# wm8804_breakout.net
KiCad netlist of a schematic drawn in EAGLE
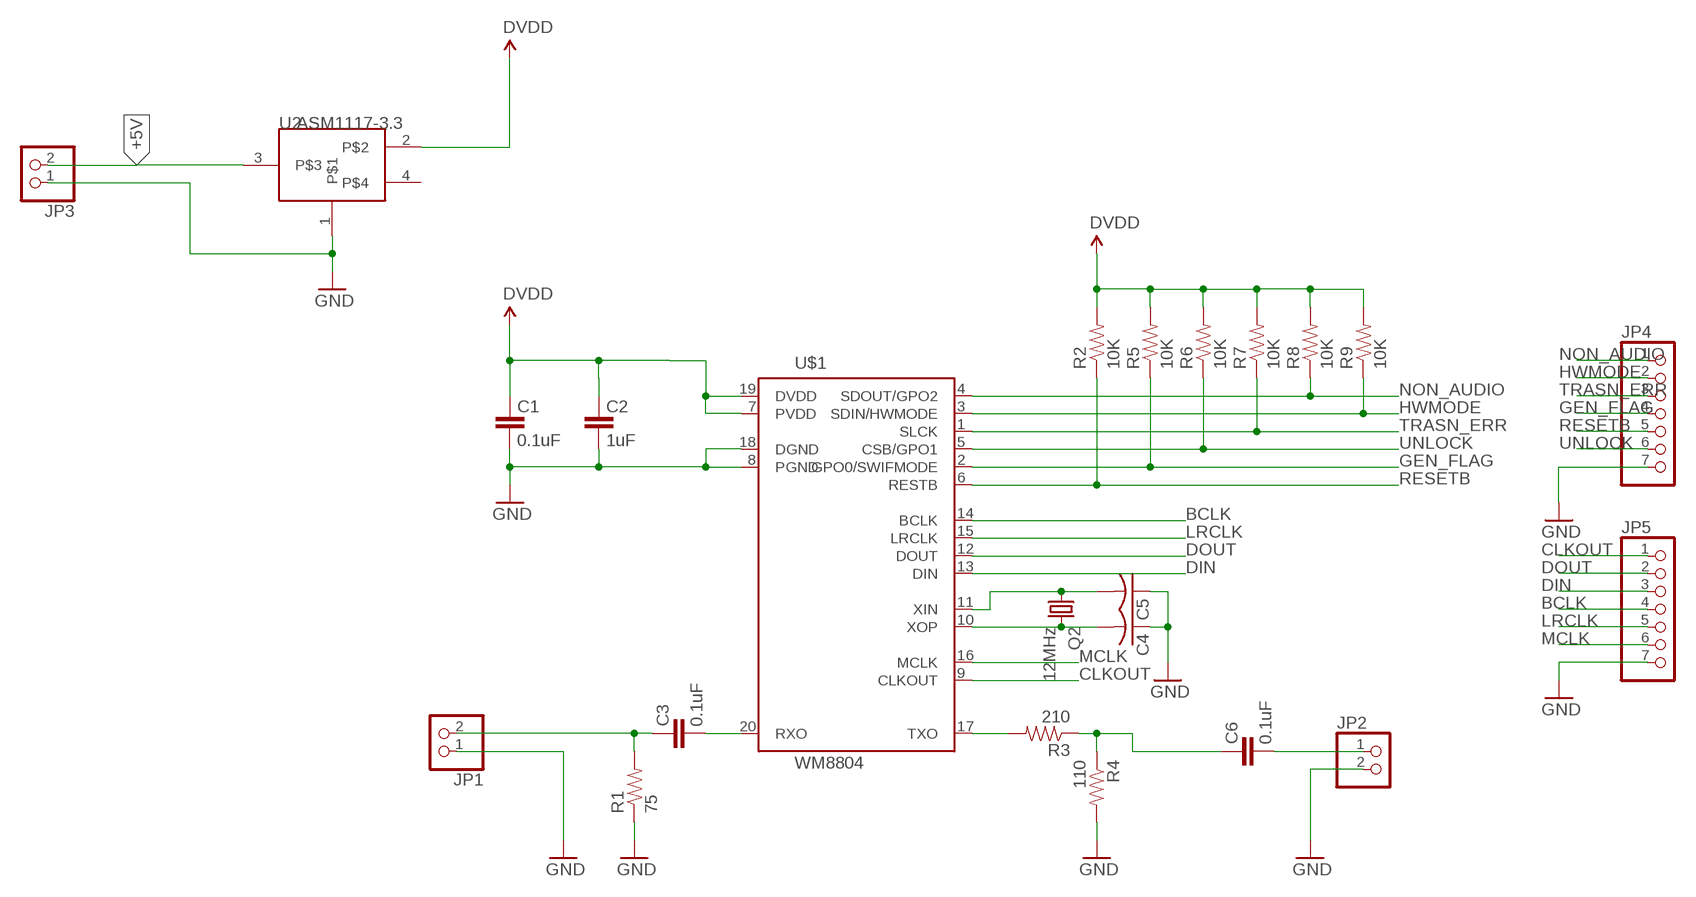
[diagram p0: schematic, sheet 1]

(export (version "E")
  (design (tool "Eeschema 10.0.6"))
  (components
    (comp (ref "C1")
      (value "0.1uF")
      (footprint "eagle-import:0805")
      (libsource (lib "eagle-import") (part "CAP0805"))
    )
    (comp (ref "C2")
      (value "1uF")
      (footprint "eagle-import:0805")
      (libsource (lib "eagle-import") (part "CAP0805"))
    )
    (comp (ref "C3")
      (value "0.1uF")
      (footprint "eagle-import:0805")
      (libsource (lib "eagle-import") (part "CAP0805"))
    )
    (comp (ref "C4")
      (value "C-USC0805")
      (footprint "eagle-import:C0805")
      (libsource (lib "eagle-import") (part "C-USC0805"))
    )
    (comp (ref "C5")
      (value "C-USC0805")
      (footprint "eagle-import:C0805")
      (libsource (lib "eagle-import") (part "C-USC0805"))
    )
    (comp (ref "C6")
      (value "0.1uF")
      (footprint "eagle-import:0805")
      (libsource (lib "eagle-import") (part "CAP0805"))
    )
    (comp (ref "JP1")
      (value "PINHD-1X2")
      (footprint "eagle-import:1X02")
      (libsource (lib "eagle-import") (part "PINHD-1X2"))
    )
    (comp (ref "JP2")
      (value "PINHD-1X2")
      (footprint "eagle-import:1X02")
      (libsource (lib "eagle-import") (part "PINHD-1X2"))
    )
    (comp (ref "JP3")
      (value "PINHD-1X2")
      (footprint "eagle-import:1X02")
      (libsource (lib "eagle-import") (part "PINHD-1X2"))
    )
    (comp (ref "JP4")
      (value "PINHD-1X7")
      (footprint "eagle-import:1X07")
      (libsource (lib "eagle-import") (part "PINHD-1X7"))
    )
    (comp (ref "JP5")
      (value "PINHD-1X7")
      (footprint "eagle-import:1X07")
      (libsource (lib "eagle-import") (part "PINHD-1X7"))
    )
    (comp (ref "Q2")
      (value "12MHz")
      (footprint "eagle-import:CTS406")
      (libsource (lib "eagle-import") (part "CRYSTALCTS406"))
    )
    (comp (ref "R1")
      (value "75")
      (footprint "eagle-import:0805")
      (libsource (lib "eagle-import") (part "RESISTOR"))
    )
    (comp (ref "R2")
      (value "10K")
      (footprint "eagle-import:0805")
      (libsource (lib "eagle-import") (part "RESISTOR"))
    )
    (comp (ref "R3")
      (value "210")
      (footprint "eagle-import:0805")
      (libsource (lib "eagle-import") (part "RESISTOR"))
    )
    (comp (ref "R4")
      (value "110")
      (footprint "eagle-import:0805")
      (libsource (lib "eagle-import") (part "RESISTOR"))
    )
    (comp (ref "R5")
      (value "10K")
      (footprint "eagle-import:0805")
      (libsource (lib "eagle-import") (part "RESISTOR"))
    )
    (comp (ref "R6")
      (value "10K")
      (footprint "eagle-import:0805")
      (libsource (lib "eagle-import") (part "RESISTOR"))
    )
    (comp (ref "R7")
      (value "10K")
      (footprint "eagle-import:0805")
      (libsource (lib "eagle-import") (part "RESISTOR"))
    )
    (comp (ref "R8")
      (value "10K")
      (footprint "eagle-import:0805")
      (libsource (lib "eagle-import") (part "RESISTOR"))
    )
    (comp (ref "R9")
      (value "10K")
      (footprint "eagle-import:0805")
      (libsource (lib "eagle-import") (part "RESISTOR"))
    )
    (comp (ref "U$1")
      (value "WM8804")
      (footprint "eagle-import:SSOP20")
      (libsource (lib "eagle-import") (part "WM8804"))
    )
    (comp (ref "U2")
      (value "ASM1117-3.3")
      (footprint "eagle-import:SOT223")
      (libsource (lib "eagle-import") (part "ASM1117-3.3"))
    )
  )
  (nets
    (net (code "1") (name "+5V") (class "Default")
      (node (ref "JP3") (pin "2") (pinfunction "2_2") (pintype "passive"))
      (node (ref "U2") (pin "3") (pinfunction "P$3_3") (pintype "bidirectional"))
    )
    (net (code "2") (name "/BCLK") (class "Default")
      (node (ref "JP5") (pin "4") (pinfunction "4_4") (pintype "passive"))
      (node (ref "U$1") (pin "14") (pinfunction "BCLK_14") (pintype "bidirectional"))
    )
    (net (code "3") (name "/CLKOUT") (class "Default")
      (node (ref "JP5") (pin "1") (pinfunction "1_1") (pintype "passive"))
      (node (ref "U$1") (pin "9") (pinfunction "CLKOUT_9") (pintype "output"))
    )
    (net (code "4") (name "/DIN") (class "Default")
      (node (ref "JP5") (pin "3") (pinfunction "3_3") (pintype "passive"))
      (node (ref "U$1") (pin "13") (pinfunction "DIN_13") (pintype "input"))
    )
    (net (code "5") (name "/DOUT") (class "Default")
      (node (ref "JP5") (pin "2") (pinfunction "2_2") (pintype "passive"))
      (node (ref "U$1") (pin "12") (pinfunction "DOUT_12") (pintype "output"))
    )
    (net (code "6") (name "/GEN_FLAG") (class "Default")
      (node (ref "JP4") (pin "4") (pinfunction "4_4") (pintype "passive"))
      (node (ref "R5") (pin "1") (pinfunction "1_1") (pintype "passive"))
      (node (ref "U$1") (pin "2") (pinfunction "GPO0/SWIFMODE_2") (pintype "output"))
    )
    (net (code "7") (name "/HWMODE") (class "Default")
      (node (ref "JP4") (pin "2") (pinfunction "2_2") (pintype "passive"))
      (node (ref "R9") (pin "1") (pinfunction "1_1") (pintype "passive"))
      (node (ref "U$1") (pin "3") (pinfunction "SDIN/HWMODE_3") (pintype "input"))
    )
    (net (code "8") (name "/LRCLK") (class "Default")
      (node (ref "JP5") (pin "5") (pinfunction "5_5") (pintype "passive"))
      (node (ref "U$1") (pin "15") (pinfunction "LRCLK_15") (pintype "bidirectional"))
    )
    (net (code "9") (name "/MCLK") (class "Default")
      (node (ref "JP5") (pin "6") (pinfunction "6_6") (pintype "passive"))
      (node (ref "U$1") (pin "16") (pinfunction "MCLK_16") (pintype "bidirectional"))
    )
    (net (code "10") (name "/NON_AUDIO") (class "Default")
      (node (ref "JP4") (pin "1") (pinfunction "1_1") (pintype "passive"))
      (node (ref "R8") (pin "1") (pinfunction "1_1") (pintype "passive"))
      (node (ref "U$1") (pin "4") (pinfunction "SDOUT/GPO2_4") (pintype "output"))
    )
    (net (code "11") (name "/RESETB") (class "Default")
      (node (ref "JP4") (pin "5") (pinfunction "5_5") (pintype "passive"))
      (node (ref "R2") (pin "1") (pinfunction "1_1") (pintype "passive"))
      (node (ref "U$1") (pin "6") (pinfunction "RESTB_6") (pintype "input"))
    )
    (net (code "12") (name "/TRASN_ERR") (class "Default")
      (node (ref "JP4") (pin "3") (pinfunction "3_3") (pintype "passive"))
      (node (ref "R7") (pin "1") (pinfunction "1_1") (pintype "passive"))
      (node (ref "U$1") (pin "1") (pinfunction "SLCK_1") (pintype "input"))
    )
    (net (code "13") (name "/UNLOCK") (class "Default")
      (node (ref "JP4") (pin "6") (pinfunction "6_6") (pintype "passive"))
      (node (ref "R6") (pin "1") (pinfunction "1_1") (pintype "passive"))
      (node (ref "U$1") (pin "5") (pinfunction "CSB/GPO1_5") (pintype "input"))
    )
    (net (code "14") (name "DVDD") (class "Default")
      (node (ref "C1") (pin "2") (pinfunction "2_2") (pintype "passive"))
      (node (ref "C2") (pin "2") (pinfunction "2_2") (pintype "passive"))
      (node (ref "R2") (pin "2") (pinfunction "2_2") (pintype "passive"))
      (node (ref "R5") (pin "2") (pinfunction "2_2") (pintype "passive"))
      (node (ref "R6") (pin "2") (pinfunction "2_2") (pintype "passive"))
      (node (ref "R7") (pin "2") (pinfunction "2_2") (pintype "passive"))
      (node (ref "R8") (pin "2") (pinfunction "2_2") (pintype "passive"))
      (node (ref "R9") (pin "2") (pinfunction "2_2") (pintype "passive"))
      (node (ref "U$1") (pin "19") (pinfunction "DVDD_19") (pintype "power_in"))
      (node (ref "U$1") (pin "7") (pinfunction "PVDD_7") (pintype "power_in"))
      (node (ref "U2") (pin "2") (pinfunction "P$2_2") (pintype "bidirectional"))
    )
    (net (code "15") (name "GND") (class "Default")
      (node (ref "C1") (pin "1") (pinfunction "1_1") (pintype "passive"))
      (node (ref "C2") (pin "1") (pinfunction "1_1") (pintype "passive"))
      (node (ref "C4") (pin "1") (pinfunction "1_1") (pintype "passive"))
      (node (ref "C5") (pin "1") (pinfunction "1_1") (pintype "passive"))
      (node (ref "JP1") (pin "1") (pinfunction "1_1") (pintype "passive"))
      (node (ref "JP2") (pin "2") (pinfunction "2_2") (pintype "passive"))
      (node (ref "JP3") (pin "1") (pinfunction "1_1") (pintype "passive"))
      (node (ref "JP4") (pin "7") (pinfunction "7_7") (pintype "passive"))
      (node (ref "JP5") (pin "7") (pinfunction "7_7") (pintype "passive"))
      (node (ref "R1") (pin "1") (pinfunction "1_1") (pintype "passive"))
      (node (ref "R4") (pin "2") (pinfunction "2_2") (pintype "passive"))
      (node (ref "U$1") (pin "18") (pinfunction "DGND_18") (pintype "power_in"))
      (node (ref "U$1") (pin "8") (pinfunction "PGND_8") (pintype "power_in"))
      (node (ref "U2") (pin "1") (pinfunction "P$1_1") (pintype "bidirectional"))
    )
    (net (code "16") (name "Net-(C3-Pad2)") (class "Default")
      (node (ref "C3") (pin "2") (pinfunction "2_2") (pintype "passive"))
      (node (ref "JP1") (pin "2") (pinfunction "2_2") (pintype "passive"))
      (node (ref "R1") (pin "2") (pinfunction "2_2") (pintype "passive"))
    )
    (net (code "17") (name "Net-(C6-Pad1)") (class "Default")
      (node (ref "C6") (pin "1") (pinfunction "1_1") (pintype "passive"))
      (node (ref "JP2") (pin "1") (pinfunction "1_1") (pintype "passive"))
    )
    (net (code "18") (name "Net-(C6-Pad2)") (class "Default")
      (node (ref "C6") (pin "2") (pinfunction "2_2") (pintype "passive"))
      (node (ref "R3") (pin "1") (pinfunction "1_1") (pintype "passive"))
      (node (ref "R4") (pin "1") (pinfunction "1_1") (pintype "passive"))
    )
    (net (code "19") (name "Net-(Q2-2)") (class "Default")
      (node (ref "C4") (pin "2") (pinfunction "2_2") (pintype "passive"))
      (node (ref "Q2") (pin "3") (pinfunction "2_3") (pintype "passive"))
      (node (ref "U$1") (pin "10") (pinfunction "XOP_10") (pintype "bidirectional"))
    )
    (net (code "20") (name "Net-(U$1-RXO)") (class "Default")
      (node (ref "C3") (pin "1") (pinfunction "1_1") (pintype "passive"))
      (node (ref "U$1") (pin "20") (pinfunction "RXO_20") (pintype "input"))
    )
    (net (code "21") (name "Net-(U$1-TXO)") (class "Default")
      (node (ref "R3") (pin "2") (pinfunction "2_2") (pintype "passive"))
      (node (ref "U$1") (pin "17") (pinfunction "TXO_17") (pintype "output"))
    )
    (net (code "22") (name "Net-(U$1-XIN)") (class "Default")
      (node (ref "C5") (pin "2") (pinfunction "2_2") (pintype "passive"))
      (node (ref "Q2") (pin "1") (pinfunction "1_1") (pintype "passive"))
      (node (ref "U$1") (pin "11") (pinfunction "XIN_11") (pintype "bidirectional"))
    )
    (net (code "23") (name "unconnected-(U2-P$4-Pad4)") (class "Default")
      (node (ref "U2") (pin "4") (pinfunction "P$4_4") (pintype "bidirectional"))
    )
  )
)
